# piskac.net
KiCad netlist of a schematic drawn in EAGLE
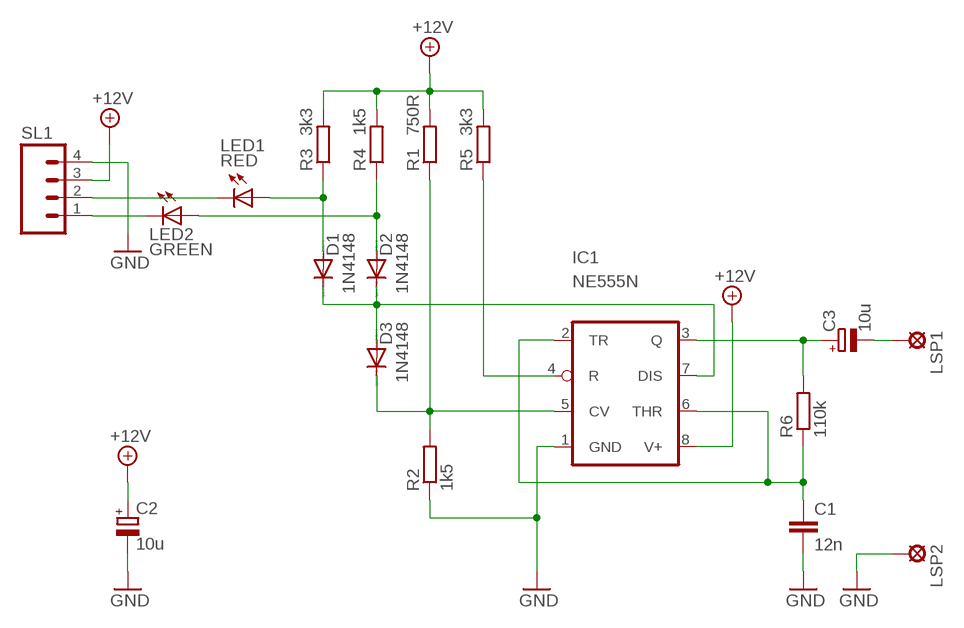
[diagram p0: schematic, sheet 1]

(export (version "E")
  (design (tool "Eeschema 10.0.6"))
  (components
    (comp (ref "C1")
      (value "12n")
      (footprint "eagle-import:C5B3.5")
      (libsource (lib "eagle-import") (part "C5/3.5"))
    )
    (comp (ref "C2")
      (value "10u")
      (footprint "eagle-import:E2,5-6")
      (libsource (lib "eagle-import") (part "CPOL-EUE2.5-6"))
    )
    (comp (ref "C3")
      (value "10u")
      (footprint "eagle-import:E2,5-6")
      (libsource (lib "eagle-import") (part "CPOL-EUE2.5-6"))
    )
    (comp (ref "D1")
      (value "1N4148")
      (footprint "eagle-import:DO35-10")
      (libsource (lib "eagle-import") (part "DIODE-DO35-10"))
    )
    (comp (ref "D2")
      (value "1N4148")
      (footprint "eagle-import:DO35-10")
      (libsource (lib "eagle-import") (part "DIODE-DO35-10"))
    )
    (comp (ref "D3")
      (value "1N4148")
      (footprint "eagle-import:DO35-10")
      (libsource (lib "eagle-import") (part "DIODE-DO35-10"))
    )
    (comp (ref "IC1")
      (value "NE555N")
      (footprint "eagle-import:DIL08")
      (libsource (lib "eagle-import") (part "555NNE"))
    )
    (comp (ref "LED1")
      (value "RED")
      (footprint "eagle-import:LED3MM")
      (libsource (lib "eagle-import") (part "LED3MM"))
    )
    (comp (ref "LED2")
      (value "GREEN")
      (footprint "eagle-import:LED3MM")
      (libsource (lib "eagle-import") (part "LED3MM"))
    )
    (comp (ref "LSP1")
      (value "LSP10")
      (footprint "eagle-import:LSP10")
      (libsource (lib "eagle-import") (part "LSP10"))
    )
    (comp (ref "LSP2")
      (value "LSP10")
      (footprint "eagle-import:LSP10")
      (libsource (lib "eagle-import") (part "LSP10"))
    )
    (comp (ref "R1")
      (value "750R")
      (footprint "eagle-import:0207_10")
      (libsource (lib "eagle-import") (part "R-EU_0207/10"))
    )
    (comp (ref "R2")
      (value "1k5")
      (footprint "eagle-import:0207_10")
      (libsource (lib "eagle-import") (part "R-EU_0207/10"))
    )
    (comp (ref "R3")
      (value "3k3")
      (footprint "eagle-import:0207_10")
      (libsource (lib "eagle-import") (part "R-EU_0207/10"))
    )
    (comp (ref "R4")
      (value "1k5")
      (footprint "eagle-import:0207_10")
      (libsource (lib "eagle-import") (part "R-EU_0207/10"))
    )
    (comp (ref "R5")
      (value "3k3")
      (footprint "eagle-import:0207_10")
      (libsource (lib "eagle-import") (part "R-EU_0207/10"))
    )
    (comp (ref "R6")
      (value "110k")
      (footprint "eagle-import:0207_10")
      (libsource (lib "eagle-import") (part "R-EU_0207/10"))
    )
    (comp (ref "SL1")
      (value "M04")
      (footprint "eagle-import:04P")
      (libsource (lib "eagle-import") (part "M04"))
    )
  )
  (nets
    (net (code "1") (name "+12V") (class "Default")
      (node (ref "C2") (pin "+") (pinfunction "+_+") (pintype "passive"))
      (node (ref "IC1") (pin "8") (pinfunction "V+_8") (pintype "power_in"))
      (node (ref "R1") (pin "2") (pinfunction "2_2") (pintype "passive"))
      (node (ref "R3") (pin "2") (pinfunction "2_2") (pintype "passive"))
      (node (ref "R4") (pin "2") (pinfunction "2_2") (pintype "passive"))
      (node (ref "R5") (pin "2") (pinfunction "2_2") (pintype "passive"))
      (node (ref "SL1") (pin "3") (pinfunction "3_3") (pintype "passive"))
    )
    (net (code "2") (name "GND") (class "Default")
      (node (ref "C1") (pin "2") (pinfunction "2_2") (pintype "passive"))
      (node (ref "C2") (pin "-") (pinfunction "-_-") (pintype "passive"))
      (node (ref "IC1") (pin "1") (pinfunction "GND_1") (pintype "power_in"))
      (node (ref "LSP2") (pin "MP") (pinfunction "MP_MP") (pintype "passive"))
      (node (ref "R2") (pin "1") (pinfunction "1_1") (pintype "passive"))
      (node (ref "SL1") (pin "4") (pinfunction "4_4") (pintype "passive"))
    )
    (net (code "3") (name "Net-(C3-Pad-)") (class "Default")
      (node (ref "C3") (pin "-") (pinfunction "-_-") (pintype "passive"))
      (node (ref "LSP1") (pin "MP") (pinfunction "MP_MP") (pintype "passive"))
    )
    (net (code "4") (name "Net-(D1-PadA)") (class "Default")
      (node (ref "D1") (pin "A") (pinfunction "A_A") (pintype "passive"))
      (node (ref "LED1") (pin "A") (pinfunction "A_A") (pintype "passive"))
      (node (ref "R3") (pin "1") (pinfunction "1_1") (pintype "passive"))
    )
    (net (code "5") (name "Net-(D2-PadA)") (class "Default")
      (node (ref "D2") (pin "A") (pinfunction "A_A") (pintype "passive"))
      (node (ref "LED2") (pin "A") (pinfunction "A_A") (pintype "passive"))
      (node (ref "R4") (pin "1") (pinfunction "1_1") (pintype "passive"))
    )
    (net (code "6") (name "Net-(IC1-CV)") (class "Default")
      (node (ref "D3") (pin "C") (pinfunction "C_C") (pintype "passive"))
      (node (ref "IC1") (pin "5") (pinfunction "CV_5") (pintype "input"))
      (node (ref "R1") (pin "1") (pinfunction "1_1") (pintype "passive"))
      (node (ref "R2") (pin "2") (pinfunction "2_2") (pintype "passive"))
    )
    (net (code "7") (name "Net-(IC1-DIS)") (class "Default")
      (node (ref "D1") (pin "C") (pinfunction "C_C") (pintype "passive"))
      (node (ref "D2") (pin "C") (pinfunction "C_C") (pintype "passive"))
      (node (ref "D3") (pin "A") (pinfunction "A_A") (pintype "passive"))
      (node (ref "IC1") (pin "7") (pinfunction "DIS_7") (pintype "input"))
    )
    (net (code "8") (name "Net-(IC1-Q)") (class "Default")
      (node (ref "C3") (pin "+") (pinfunction "+_+") (pintype "passive"))
      (node (ref "IC1") (pin "3") (pinfunction "Q_3") (pintype "output"))
      (node (ref "R6") (pin "2") (pinfunction "2_2") (pintype "passive"))
    )
    (net (code "9") (name "Net-(IC1-R)") (class "Default")
      (node (ref "IC1") (pin "4") (pinfunction "R_4") (pintype "input"))
      (node (ref "R5") (pin "1") (pinfunction "1_1") (pintype "passive"))
    )
    (net (code "10") (name "Net-(IC1-THR)") (class "Default")
      (node (ref "C1") (pin "1") (pinfunction "1_1") (pintype "passive"))
      (node (ref "IC1") (pin "2") (pinfunction "TR_2") (pintype "input"))
      (node (ref "IC1") (pin "6") (pinfunction "THR_6") (pintype "input"))
      (node (ref "R6") (pin "1") (pinfunction "1_1") (pintype "passive"))
    )
    (net (code "11") (name "Net-(LED1-C)") (class "Default")
      (node (ref "LED1") (pin "K") (pinfunction "C_K") (pintype "passive"))
      (node (ref "SL1") (pin "2") (pinfunction "2_2") (pintype "passive"))
    )
    (net (code "12") (name "Net-(LED2-C)") (class "Default")
      (node (ref "LED2") (pin "K") (pinfunction "C_K") (pintype "passive"))
      (node (ref "SL1") (pin "1") (pinfunction "1_1") (pintype "passive"))
    )
  )
)
